# USBC_PD_Controller.net
KiCad netlist of a schematic drawn in Altium Designer
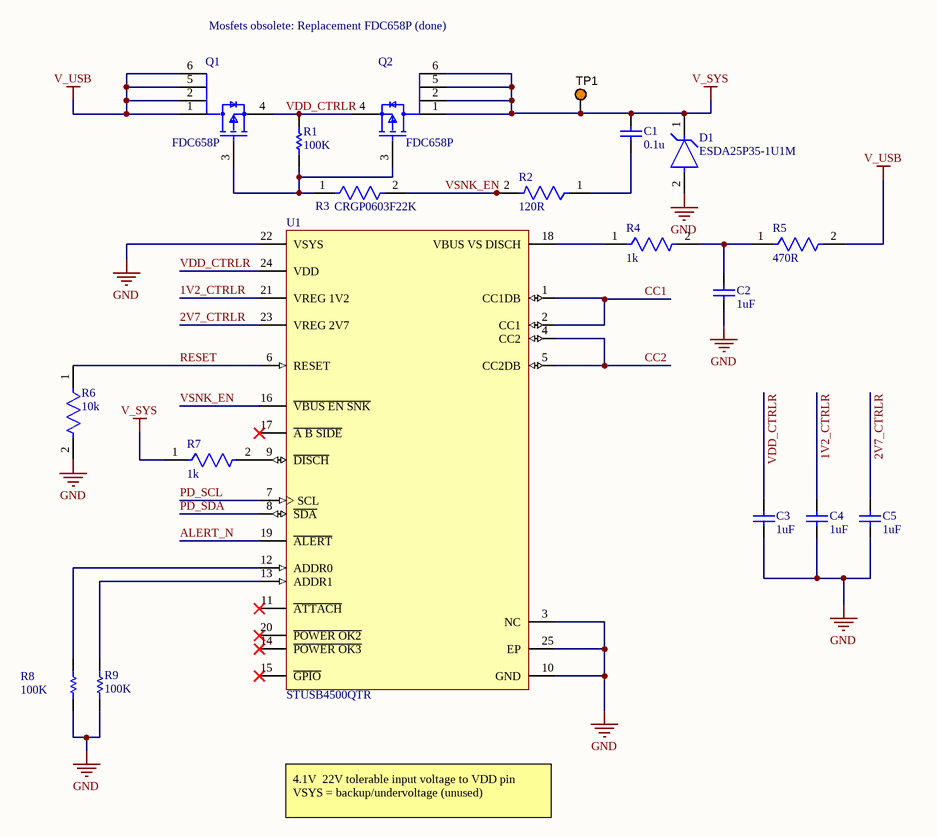
[diagram p0: USBC_PD_Controller.SchDoc]

(export (version "E")
  (design (tool "Eeschema 10.0.6"))
  (components
    (comp (ref "C1")
      (value "0.1u")
      (footprint "CAPC2013X140X50ML20T25")
      (fields
        (field (name "PART NUMBER") "0805DD104KAT2A")
        (field (name "MANUFACTURER") "AVX Interconnect / Elco")
      )
      (libsource (lib "Altium Content Vault") (part "CAP"))
    )
    (comp (ref "C2")
      (value "1uF")
      (footprint "CAPC2013X145X50NL20T20")
      (fields (field (name "PART NUMBER") "VJ0805Y105KXQRW1BC") (field (name "MANUFACTURER") "Vitramon"))
      (libsource (lib "Altium Content Vault") (part "CAP"))
    )
    (comp (ref "C3")
      (value "1uF")
      (footprint "CAPC2013X145X50NL20T20")
      (fields (field (name "PART NUMBER") "VJ0805Y105KXQRW1BC") (field (name "MANUFACTURER") "Vitramon"))
      (libsource (lib "Altium Content Vault") (part "CAP"))
    )
    (comp (ref "C4")
      (value "1uF")
      (footprint "CAPC2013X145X50NL20T20")
      (fields (field (name "PART NUMBER") "VJ0805Y105KXQRW1BC") (field (name "MANUFACTURER") "Vitramon"))
      (libsource (lib "Altium Content Vault") (part "CAP"))
    )
    (comp (ref "C5")
      (value "1uF")
      (footprint "CAPC2013X145X50NL20T20")
      (fields (field (name "PART NUMBER") "VJ0805Y105KXQRW1BC") (field (name "MANUFACTURER") "Vitramon"))
      (libsource (lib "Altium Content Vault") (part "CAP"))
    )
    (comp (ref "D1")
      (value "ESDA25P35-1U1M")
      (footprint "FP-QFN_1610-MFG")
      (description "TVS DIODE 22V 41V 1610")
      (fields
        (field (name "OCTOPART") "https://octopart.com/esda25p35-1u1m-stmicroelectronics-75302699")
        (field (name "MANUFACTURER") "STMicroelectronics")
      )
      (libsource (lib "Altium Content Vault") (part "f813f71cba58e380607f5dd3caf9714"))
    )
    (comp (ref "Q1")
      (value "FDC658P")
      (footprint "FP-419BL-MFG")
      (description "MOSFET P-CH 30V 4A SSOT-6")
      (fields
        (field (name "OCTOPART") "https://octopart.com/fdc658p-on+semiconductor-84325768")
        (field (name "MANUFACTURER") "ON Semiconductor")
      )
      (libsource (lib "Altium Content Vault") (part "04747eaf7477cc0132fdf71f34bdb77"))
    )
    (comp (ref "Q2")
      (value "FDC658P")
      (footprint "FP-419BL-MFG")
      (description "MOSFET P-CH 30V 4A SSOT-6")
      (fields
        (field (name "OCTOPART") "https://octopart.com/fdc658p-on+semiconductor-84325768")
        (field (name "MANUFACTURER") "ON Semiconductor")
      )
      (libsource (lib "Altium Content Vault") (part "04747eaf7477cc0132fdf71f34bdb77"))
    )
    (comp (ref "R1")
      (value "100K")
      (footprint "RESC0603(1608)_N")
      (description "100K 0.1W 1% 0603 (1608 Metric)  SMD")
      (fields (field (name "POWER") "0.1 W") (field (name "TOLERANCE") "1 %"))
      (libsource (lib "Altium Content Vault") (part "RES"))
    )
    (comp (ref "R2")
      (value "120R")
      (footprint "FP-SR0603-MFG")
      (description "RES SMD 0603 1/4W 1% 120 OHM")
      (fields
        (field (name "OCTOPART") "https://octopart.com/sr0603fr-7t120rl-yageo-92673849")
        (field (name "MANUFACTURER") "Yageo")
      )
      (libsource (lib "Altium Content Vault") (part "1029c3af85768c4190bb7ad29bc67b5"))
    )
    (comp (ref "R3")
      (value "CRGP0603F22K")
      (footprint "FP-CRGP0603-IPC_C")
      (description "CRGP 0603 22K 1%")
      (fields
        (field (name "OCTOPART") "https://octopart.com/crgp0603f22k-te+connectivity-91018742")
        (field (name "TOLERANCE") "0.01")
      )
      (libsource (lib "Altium Content Vault") (part "1029c3af85768c4190bb7ad29bc67b5"))
    )
    (comp (ref "R4")
      (value "1k")
      (footprint "FP-MCT0603-IPC_C")
      (description "RES SMD 100 OHM 1% 1/8W 0603")
      (fields (field (name "TOLERANCE") "0.1%"))
      (libsource (lib "Altium Content Vault") (part "1029c3af85768c4190bb7ad29bc67b5"))
    )
    (comp (ref "R5")
      (value "470R")
      (footprint "FP-CRCW0603-HPe3-MFG")
      (description "RES Thick Film, 470Ω, 5%, 0.33W, 200ppm/°C, 0603")
      (fields (field (name "TOLERANCE") "5%"))
      (libsource (lib "Altium Content Vault") (part "1029c3af85768c4190bb7ad29bc67b5"))
    )
    (comp (ref "R6")
      (value "10k")
      (footprint "FP-CRCW0603-e3-IPC_A")
      (description "RES Thick Film, 10kΩ, 1%, 0.1W, 100ppm/°C, 0603")
      (fields (field (name "TOLERANCE") "1%"))
      (libsource (lib "Altium Content Vault") (part "1029c3af85768c4190bb7ad29bc67b5"))
    )
    (comp (ref "R7")
      (value "1k")
      (footprint "FP-MCT0603-IPC_C")
      (description "RES SMD 100 OHM 1% 1/8W 0603")
      (fields (field (name "TOLERANCE") "0.1%"))
      (libsource (lib "Altium Content Vault") (part "1029c3af85768c4190bb7ad29bc67b5"))
    )
    (comp (ref "R8")
      (value "100K")
      (footprint "RESC0603(1608)_N")
      (description "100K 0.1W 1% 0603 (1608 Metric)  SMD")
      (fields (field (name "POWER") "0.1 W") (field (name "TOLERANCE") "1 %"))
      (libsource (lib "Altium Content Vault") (part "RES"))
    )
    (comp (ref "R9")
      (value "100K")
      (footprint "RESC0603(1608)_N")
      (description "100K 0.1W 1% 0603 (1608 Metric)  SMD")
      (fields (field (name "POWER") "0.1 W") (field (name "TOLERANCE") "1 %"))
      (libsource (lib "Altium Content Vault") (part "RES"))
    )
    (comp (ref "TP1")
      (value "5003")
      (footprint "KSTN-5003")
      (description "Test Point, Orange, 1-Pin THD, RoHS")
      (libsource (lib "Altium Content Vault") (part "TESTPOINT_ORANGE"))
    )
    (comp (ref "U1")
      (value "STUSB4500QTR")
      (footprint "FP-QFN-24-EP_4x4-MFG")
      (description "4.1V~22V USB 2.0 I2C Controllers Interface ICs STUSB45 Controller 24-VFQFN Exposed Pad")
      (libsource (lib "Altium Content Vault") (part "STUSB4500QTR"))
    )
  )
  (nets
    (net (code "1") (name "/1V2_CTRLR") (class "Default")
      (node (ref "C4") (pin "1") (pinfunction "1_1") (pintype "passive"))
      (node (ref "U1") (pin "21") (pinfunction "VREG_1V2_21") (pintype "power_in"))
    )
    (net (code "2") (name "/2V7_CTRLR") (class "Default")
      (node (ref "C5") (pin "1") (pinfunction "1_1") (pintype "passive"))
      (node (ref "U1") (pin "23") (pinfunction "VREG_2V7_23") (pintype "power_in"))
    )
    (net (code "3") (name "/ALERT_N") (class "Default")
      (node (ref "U1") (pin "19") (pinfunction "~{ALERT}_19") (pintype "open_collector"))
    )
    (net (code "4") (name "/CC1") (class "Default")
      (node (ref "U1") (pin "1") (pinfunction "CC1DB_1") (pintype "bidirectional"))
      (node (ref "U1") (pin "2") (pinfunction "CC1_2") (pintype "bidirectional"))
    )
    (net (code "5") (name "/CC2") (class "Default")
      (node (ref "U1") (pin "4") (pinfunction "CC2_4") (pintype "bidirectional"))
      (node (ref "U1") (pin "5") (pinfunction "CC2DB_5") (pintype "bidirectional"))
    )
    (net (code "6") (name "/PD_SCL") (class "Default")
      (node (ref "U1") (pin "7") (pinfunction "SCL_7") (pintype "input"))
    )
    (net (code "7") (name "/PD_SDA") (class "Default")
      (node (ref "U1") (pin "8") (pinfunction "~{SDA}_8") (pintype "bidirectional"))
    )
    (net (code "8") (name "/RESET") (class "Default")
      (node (ref "R6") (pin "1") (pinfunction "1_1") (pintype "passive"))
      (node (ref "U1") (pin "6") (pinfunction "RESET_6") (pintype "input"))
    )
    (net (code "9") (name "/VDD_CTRLR") (class "Default")
      (node (ref "C3") (pin "1") (pinfunction "1_1") (pintype "passive"))
      (node (ref "Q1") (pin "4") (pinfunction "S_4") (pintype "passive"))
      (node (ref "Q2") (pin "4") (pinfunction "S_4") (pintype "passive"))
      (node (ref "R1") (pin "2") (pinfunction "2_2") (pintype "passive"))
      (node (ref "U1") (pin "24") (pinfunction "VDD_24") (pintype "power_in"))
    )
    (net (code "10") (name "/VSNK_EN") (class "Default")
      (node (ref "R2") (pin "2") (pinfunction "2_2") (pintype "passive"))
      (node (ref "R3") (pin "2") (pinfunction "2_2") (pintype "passive"))
      (node (ref "U1") (pin "16") (pinfunction "~{VBUS_EN_SNK}_16") (pintype "open_collector"))
    )
    (net (code "11") (name "GND") (class "Default")
      (node (ref "C2") (pin "2") (pinfunction "2_2") (pintype "passive"))
      (node (ref "C3") (pin "2") (pinfunction "2_2") (pintype "passive"))
      (node (ref "C4") (pin "2") (pinfunction "2_2") (pintype "passive"))
      (node (ref "C5") (pin "2") (pinfunction "2_2") (pintype "passive"))
      (node (ref "D1") (pin "2") (pinfunction "A_2") (pintype "passive"))
      (node (ref "R6") (pin "2") (pinfunction "2_2") (pintype "passive"))
      (node (ref "R8") (pin "1") (pinfunction "1_1") (pintype "passive"))
      (node (ref "R9") (pin "1") (pinfunction "1_1") (pintype "passive"))
      (node (ref "U1") (pin "10") (pinfunction "GND_10") (pintype "power_in"))
      (node (ref "U1") (pin "22") (pinfunction "VSYS_22") (pintype "power_in"))
      (node (ref "U1") (pin "25") (pinfunction "EP_25") (pintype "power_in"))
      (node (ref "U1") (pin "3") (pinfunction "NC_3") (pintype "passive"))
    )
    (net (code "12") (name "Net-(C1-Pad2)") (class "Default")
      (node (ref "C1") (pin "2") (pinfunction "2_2") (pintype "passive"))
      (node (ref "R2") (pin "1") (pinfunction "1_1") (pintype "passive"))
    )
    (net (code "13") (name "Net-(C2-Pad1)") (class "Default")
      (node (ref "C2") (pin "1") (pinfunction "1_1") (pintype "passive"))
      (node (ref "R4") (pin "2") (pinfunction "2_2") (pintype "passive"))
      (node (ref "R5") (pin "1") (pinfunction "1_1") (pintype "passive"))
    )
    (net (code "14") (name "Net-(Q1-G)") (class "Default")
      (node (ref "Q1") (pin "3") (pinfunction "G_3") (pintype "passive"))
      (node (ref "Q2") (pin "3") (pinfunction "G_3") (pintype "passive"))
      (node (ref "R1") (pin "1") (pinfunction "1_1") (pintype "passive"))
      (node (ref "R3") (pin "1") (pinfunction "1_1") (pintype "passive"))
    )
    (net (code "15") (name "Net-(U1-ADDR0)") (class "Default")
      (node (ref "R8") (pin "2") (pinfunction "2_2") (pintype "passive"))
      (node (ref "U1") (pin "12") (pinfunction "ADDR0_12") (pintype "input"))
    )
    (net (code "16") (name "Net-(U1-ADDR1)") (class "Default")
      (node (ref "R9") (pin "2") (pinfunction "2_2") (pintype "passive"))
      (node (ref "U1") (pin "13") (pinfunction "ADDR1_13") (pintype "input"))
    )
    (net (code "17") (name "Net-(U1-VBUS_VS_DISCH)") (class "Default")
      (node (ref "R4") (pin "1") (pinfunction "1_1") (pintype "passive"))
      (node (ref "U1") (pin "18") (pinfunction "VBUS_VS_DISCH_18") (pintype "power_in"))
    )
    (net (code "18") (name "Net-(U1-~{DISCH})") (class "Default")
      (node (ref "R7") (pin "2") (pinfunction "2_2") (pintype "passive"))
      (node (ref "U1") (pin "9") (pinfunction "~{DISCH}_9") (pintype "bidirectional"))
    )
    (net (code "19") (name "V_SYS") (class "Default")
      (node (ref "C1") (pin "1") (pinfunction "1_1") (pintype "passive"))
      (node (ref "D1") (pin "1") (pinfunction "C_1") (pintype "passive"))
      (node (ref "Q2") (pin "1") (pinfunction "D_1") (pintype "passive"))
      (node (ref "Q2") (pin "2") (pinfunction "D_2") (pintype "passive"))
      (node (ref "Q2") (pin "5") (pinfunction "D_5") (pintype "passive"))
      (node (ref "Q2") (pin "6") (pinfunction "D_6") (pintype "passive"))
      (node (ref "R7") (pin "1") (pinfunction "1_1") (pintype "passive"))
      (node (ref "TP1") (pin "1") (pinfunction "1_1") (pintype "passive"))
    )
    (net (code "20") (name "V_USB") (class "Default")
      (node (ref "Q1") (pin "1") (pinfunction "D_1") (pintype "passive"))
      (node (ref "Q1") (pin "2") (pinfunction "D_2") (pintype "passive"))
      (node (ref "Q1") (pin "5") (pinfunction "D_5") (pintype "passive"))
      (node (ref "Q1") (pin "6") (pinfunction "D_6") (pintype "passive"))
      (node (ref "R5") (pin "2") (pinfunction "2_2") (pintype "passive"))
    )
    (net (code "21") (name "unconnected-(U1-~{ATTACH}-Pad11)") (class "Default")
      (node (ref "U1") (pin "11") (pinfunction "~{ATTACH}_11") (pintype "open_collector+no_connect"))
    )
    (net (code "22") (name "unconnected-(U1-~{A_B_SIDE}-Pad17)") (class "Default")
      (node (ref "U1") (pin "17") (pinfunction "~{A_B_SIDE}_17") (pintype "open_collector+no_connect"))
    )
    (net (code "23") (name "unconnected-(U1-~{GPIO}-Pad15)") (class "Default")
      (node (ref "U1") (pin "15") (pinfunction "~{GPIO}_15") (pintype "open_collector+no_connect"))
    )
    (net (code "24") (name "unconnected-(U1-~{POWER_OK2}-Pad20)") (class "Default")
      (node (ref "U1") (pin "20") (pinfunction "~{POWER_OK2}_20") (pintype "power_in+no_connect"))
    )
    (net (code "25") (name "unconnected-(U1-~{POWER_OK3}-Pad14)") (class "Default")
      (node (ref "U1") (pin "14") (pinfunction "~{POWER_OK3}_14") (pintype "open_collector+no_connect"))
    )
  )
)
